# CH32V002J4M6.net
KiCad netlist of a schematic drawn in Altium Designer
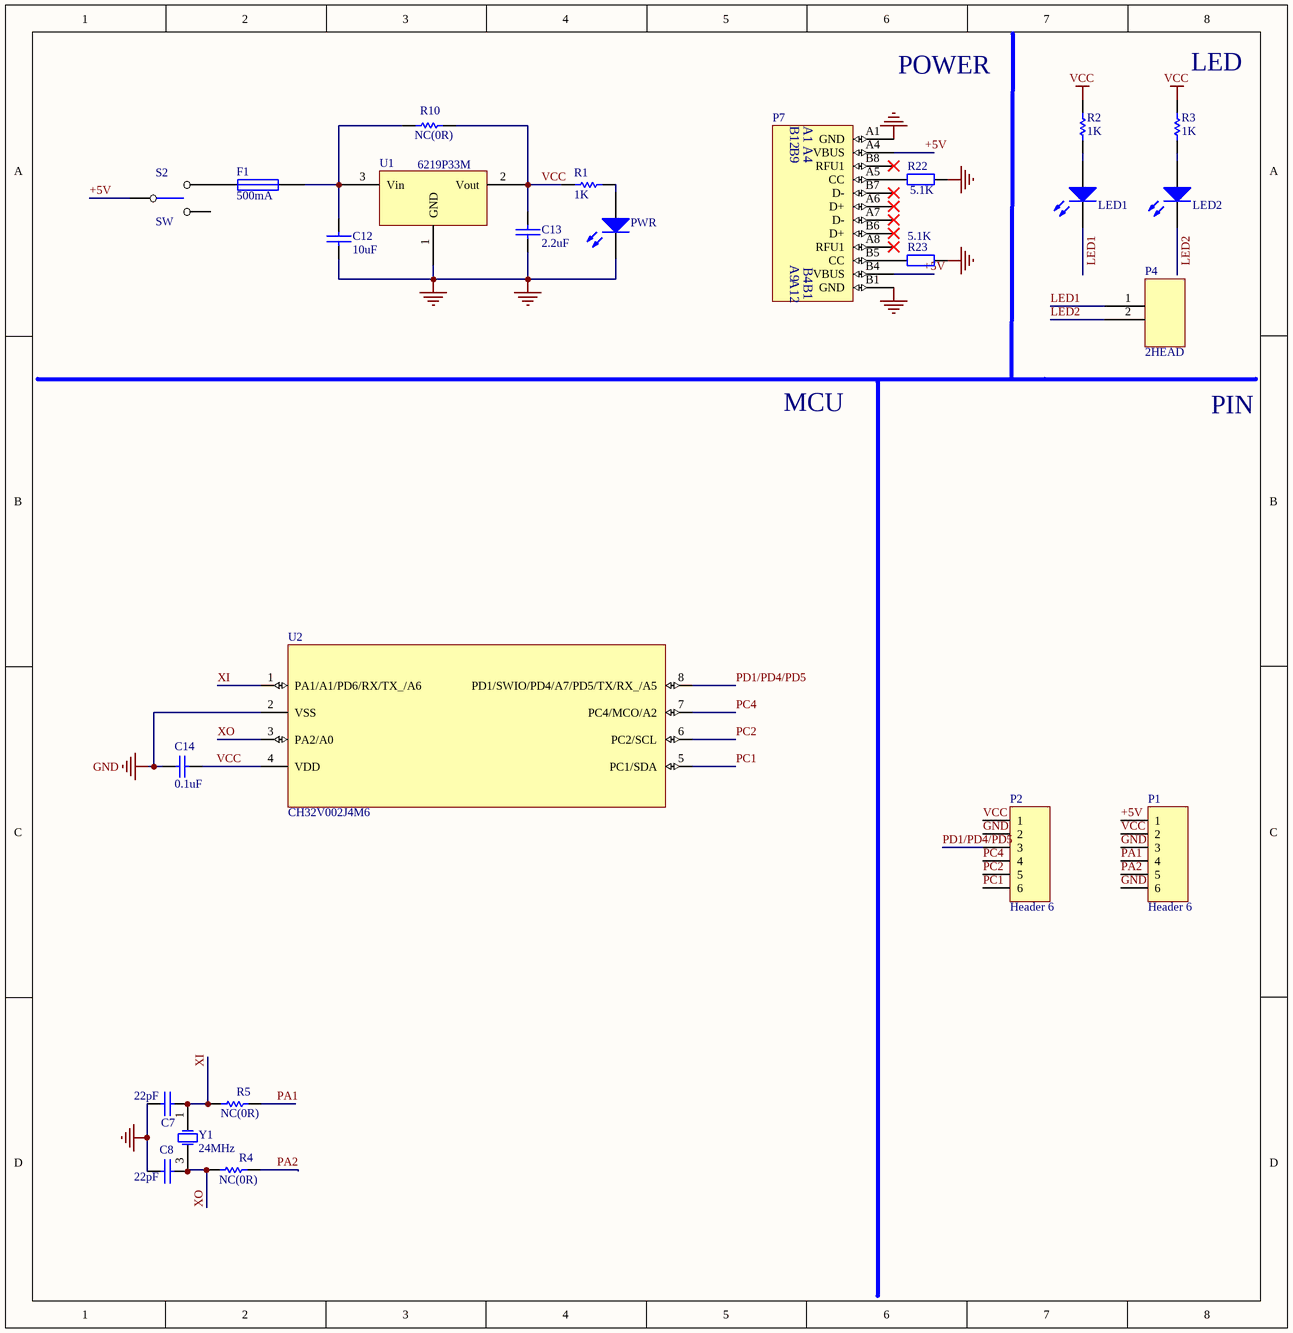
[diagram p0: CH32V002J4M6.SchDoc]

(export (version "E")
  (design (tool "Eeschema 10.0.6"))
  (components
    (comp (ref "C7")
      (value "22pF")
      (footprint "0402_C")
      (description "Capacitor")
      (libsource (lib "*") (part "CAP"))
    )
    (comp (ref "C8")
      (value "22pF")
      (footprint "0402_C")
      (description "Capacitor")
      (libsource (lib "*") (part "CAP"))
    )
    (comp (ref "C12")
      (value "10uF")
      (footprint "0603_C")
      (description "Capacitor")
      (libsource (lib "wch_sch_others") (part "CAP"))
    )
    (comp (ref "C13")
      (value "2.2uF")
      (footprint "0402_C")
      (description "Capacitor")
      (libsource (lib "wch_sch_others") (part "CAP"))
    )
    (comp (ref "C14")
      (value "0.1uF")
      (footprint "0603_C")
      (description "Capacitor")
      (fields (field (name "PUBLISHER") "Altium Limited"))
      (libsource (lib "*") (part "Cap"))
    )
    (comp (ref "F1")
      (value "500mA")
      (footprint "0603")
      (description "Fuse")
      (libsource (lib "*") (part "FUSE1"))
    )
    (comp (ref "LED1")
      (value "LED1   blue")
      (footprint "0603+")
      (description "Typical INFRARED GaAs LED")
      (fields (field (name "PUBLISHER") "Altium Limited"))
      (libsource (lib "") (part "LED0_1"))
    )
    (comp (ref "LED2")
      (value "LED2  blue")
      (footprint "0603+")
      (description "Typical INFRARED GaAs LED")
      (fields (field (name "PUBLISHER") "Altium Limited"))
      (libsource (lib "") (part "LED0_1"))
    )
    (comp (ref "P1")
      (value "Header 6")
      (footprint "HDR1X6")
      (description "Header, 6-Pin")
      (fields (field (name "PUBLISHER") "Altium Limited"))
      (libsource (lib "Miscellaneous Connectors") (part "Header 6"))
    )
    (comp (ref "P2")
      (value "Header 6")
      (footprint "HDR1X6")
      (description "Header, 6-Pin")
      (fields (field (name "PUBLISHER") "Altium Limited"))
      (libsource (lib "Miscellaneous Connectors") (part "Header 6"))
    )
    (comp (ref "P4") (value "2HEAD") (footprint "SIP2-2.54mm") (libsource (lib "*") (part "2HEAD")))
    (comp (ref "P7")
      (value "TYPE-C")
      (footprint "TYPE-C-Receptacle-2.0")
      (libsource (lib "*") (part "TYPE-C1"))
    )
    (comp (ref "PWR")
      (value "POWER  red")
      (footprint "0603+")
      (description "Typical INFRARED GaAs LED")
      (fields (field (name "PUBLISHER") "Altium Limited"))
      (libsource (lib "*") (part "LED0"))
    )
    (comp (ref "R1")
      (value "1K")
      (footprint "0402")
      (description "Semiconductor Resistor")
      (fields (field (name "PUBLISHER") "Altium Limited"))
      (libsource (lib "*") (part "Res Semi"))
    )
    (comp (ref "R2")
      (value "1K")
      (footprint "0402")
      (description "Semiconductor Resistor")
      (fields (field (name "PUBLISHER") "Altium Limited"))
      (libsource (lib "*") (part "Res Semi"))
    )
    (comp (ref "R3")
      (value "1K")
      (footprint "0402")
      (description "Semiconductor Resistor")
      (fields (field (name "PUBLISHER") "Altium Limited"))
      (libsource (lib "*") (part "Res Semi"))
    )
    (comp (ref "R4")
      (value "NC(0R)")
      (footprint "0402")
      (description "Semiconductor Resistor")
      (fields (field (name "Comment") "0R") (field (name "PUBLISHER") "Altium Limited"))
      (libsource (lib "*") (part "Res Semi"))
    )
    (comp (ref "R5")
      (value "NC(0R)")
      (footprint "0402")
      (description "Semiconductor Resistor")
      (fields (field (name "Comment") "0R") (field (name "PUBLISHER") "Altium Limited"))
      (libsource (lib "*") (part "Res Semi"))
    )
    (comp (ref "R10")
      (value "NC(0R)")
      (footprint "0402")
      (description "Semiconductor Resistor")
      (fields (field (name "Comment") "0R") (field (name "PUBLISHER") "Altium Limited"))
      (libsource (lib "*") (part "Res Semi"))
    )
    (comp (ref "R22")
      (value "5.1K")
      (footprint "0402")
      (description "Resistor")
      (libsource (lib "Miscellaneous Devices") (part "Res2"))
    )
    (comp (ref "R23")
      (value "5.1K")
      (footprint "0402")
      (description "Resistor")
      (libsource (lib "Miscellaneous Devices") (part "Res2"))
    )
    (comp (ref "S2") (value "SW") (footprint "SW1") (libsource (lib "*") (part "SW")))
    (comp (ref "U1")
      (value "6219P33M")
      (footprint "SOT-23")
      (libsource (lib "wch_sch_others") (part "6219P33M"))
    )
    (comp (ref "U2")
      (value "CH32V002J4M6")
      (footprint "SOP8")
      (description "RISC-V MCU, 48MHz, ADC/UART/I2C")
      (libsource (lib "DHXXXSCH") (part "CH32V002J4M6"))
    )
    (comp (ref "Y1")
      (value "24MHz")
      (footprint "XT3225")
      (description "Crystal Oscillator")
      (fields (field (name "PUBLISHER") "Altium Limited"))
      (libsource (lib "*") (part "XTAL"))
    )
  )
  (nets
    (net (code "1") (name "/+5V") (class "Default")
      (node (ref "P1") (pin "1") (pinfunction "1_1") (pintype "passive"))
      (node (ref "P7") (pin "A4") (pinfunction "VBUS_A4") (pintype "bidirectional"))
      (node (ref "P7") (pin "B4") (pinfunction "VBUS_B4") (pintype "bidirectional"))
      (node (ref "S2") (pin "1") (pinfunction "1_1") (pintype "passive"))
    )
    (net (code "2") (name "/LED1") (class "Default")
      (node (ref "LED1") (pin "2") (pinfunction "K_2") (pintype "passive"))
      (node (ref "P4") (pin "1") (pintype "passive"))
    )
    (net (code "3") (name "/LED2") (class "Default")
      (node (ref "LED2") (pin "2") (pinfunction "K_2") (pintype "passive"))
      (node (ref "P4") (pin "2") (pintype "passive"))
    )
    (net (code "4") (name "/PA1") (class "Default")
      (node (ref "P1") (pin "4") (pinfunction "4_4") (pintype "passive"))
      (node (ref "R5") (pin "2") (pinfunction "2_2") (pintype "passive"))
    )
    (net (code "5") (name "/PA2") (class "Default")
      (node (ref "P1") (pin "5") (pinfunction "5_5") (pintype "passive"))
      (node (ref "R4") (pin "2") (pinfunction "2_2") (pintype "passive"))
    )
    (net (code "6") (name "/PC1") (class "Default")
      (node (ref "P2") (pin "6") (pinfunction "6_6") (pintype "passive"))
      (node (ref "U2") (pin "5") (pinfunction "PC1/SDA_5") (pintype "bidirectional"))
    )
    (net (code "7") (name "/PC2") (class "Default")
      (node (ref "P2") (pin "5") (pinfunction "5_5") (pintype "passive"))
      (node (ref "U2") (pin "6") (pinfunction "PC2/SCL_6") (pintype "bidirectional"))
    )
    (net (code "8") (name "/PC4") (class "Default")
      (node (ref "P2") (pin "4") (pinfunction "4_4") (pintype "passive"))
      (node (ref "U2") (pin "7") (pinfunction "PC4/MCO/A2_7") (pintype "bidirectional"))
    )
    (net (code "9") (name "/PD1{slash}PD4{slash}PD5") (class "Default")
      (node (ref "P2") (pin "3") (pinfunction "3_3") (pintype "passive"))
      (node (ref "U2") (pin "8") (pinfunction "PD1/SWIO/PD4/A7/PD5/TX/RX_/A5_8") (pintype "bidirectional"))
    )
    (net (code "10") (name "/XI") (class "Default")
      (node (ref "C7") (pin "2") (pinfunction "2_2") (pintype "passive"))
      (node (ref "R5") (pin "1") (pinfunction "1_1") (pintype "passive"))
      (node (ref "U2") (pin "1") (pinfunction "PA1/A1/PD6/RX/TX_/A6_1") (pintype "bidirectional"))
      (node (ref "Y1") (pin "1") (pinfunction "OSC1_1") (pintype "passive"))
    )
    (net (code "11") (name "/XO") (class "Default")
      (node (ref "C8") (pin "2") (pinfunction "2_2") (pintype "passive"))
      (node (ref "R4") (pin "1") (pinfunction "1_1") (pintype "passive"))
      (node (ref "U2") (pin "3") (pinfunction "PA2/A0_3") (pintype "bidirectional"))
      (node (ref "Y1") (pin "3") (pinfunction "OSC2_3") (pintype "passive"))
    )
    (net (code "12") (name "GND") (class "Default")
      (node (ref "C12") (pin "2") (pinfunction "2_2") (pintype "passive"))
      (node (ref "C13") (pin "1") (pinfunction "1_1") (pintype "passive"))
      (node (ref "C14") (pin "2") (pinfunction "2_2") (pintype "passive"))
      (node (ref "C7") (pin "1") (pinfunction "1_1") (pintype "passive"))
      (node (ref "C8") (pin "1") (pinfunction "1_1") (pintype "passive"))
      (node (ref "P1") (pin "3") (pinfunction "3_3") (pintype "passive"))
      (node (ref "P1") (pin "6") (pinfunction "6_6") (pintype "passive"))
      (node (ref "P2") (pin "2") (pinfunction "2_2") (pintype "passive"))
      (node (ref "P7") (pin "A1") (pinfunction "GND_A1") (pintype "bidirectional"))
      (node (ref "P7") (pin "B1") (pinfunction "GND_B1") (pintype "bidirectional"))
      (node (ref "PWR") (pin "2") (pinfunction "K_2") (pintype "passive"))
      (node (ref "R22") (pin "2") (pinfunction "2_2") (pintype "passive"))
      (node (ref "R23") (pin "2") (pinfunction "2_2") (pintype "passive"))
      (node (ref "U1") (pin "1") (pinfunction "GND_1") (pintype "passive"))
      (node (ref "U2") (pin "2") (pinfunction "VSS_2") (pintype "power_in"))
    )
    (net (code "13") (name "Net-(F1-Pad1)") (class "Default")
      (node (ref "F1") (pin "1") (pinfunction "1_1") (pintype "passive"))
      (node (ref "S2") (pin "3") (pinfunction "3_3") (pintype "passive"))
    )
    (net (code "14") (name "Net-(LED1-A)") (class "Default")
      (node (ref "LED1") (pin "1") (pinfunction "A_1") (pintype "passive"))
      (node (ref "R2") (pin "2") (pinfunction "2_2") (pintype "passive"))
    )
    (net (code "15") (name "Net-(LED2-A)") (class "Default")
      (node (ref "LED2") (pin "1") (pinfunction "A_1") (pintype "passive"))
      (node (ref "R3") (pin "2") (pinfunction "2_2") (pintype "passive"))
    )
    (net (code "16") (name "Net-(P7-CC-PadA5)") (class "Default")
      (node (ref "P7") (pin "A5") (pinfunction "CC_A5") (pintype "bidirectional"))
      (node (ref "R22") (pin "1") (pinfunction "1_1") (pintype "passive"))
    )
    (net (code "17") (name "Net-(P7-CC-PadB5)") (class "Default")
      (node (ref "P7") (pin "B5") (pinfunction "CC_B5") (pintype "bidirectional"))
      (node (ref "R23") (pin "1") (pinfunction "1_1") (pintype "passive"))
    )
    (net (code "18") (name "Net-(PWR-A)") (class "Default")
      (node (ref "PWR") (pin "1") (pinfunction "A_1") (pintype "passive"))
      (node (ref "R1") (pin "1") (pinfunction "1_1") (pintype "passive"))
    )
    (net (code "19") (name "Net-(U1-Vin)") (class "Default")
      (node (ref "C12") (pin "1") (pinfunction "1_1") (pintype "passive"))
      (node (ref "F1") (pin "2") (pinfunction "2_2") (pintype "passive"))
      (node (ref "R10") (pin "1") (pinfunction "1_1") (pintype "passive"))
      (node (ref "U1") (pin "3") (pinfunction "Vin_3") (pintype "passive"))
    )
    (net (code "20") (name "VCC") (class "Default")
      (node (ref "C13") (pin "2") (pinfunction "2_2") (pintype "passive"))
      (node (ref "C14") (pin "1") (pinfunction "1_1") (pintype "passive"))
      (node (ref "P1") (pin "2") (pinfunction "2_2") (pintype "passive"))
      (node (ref "P2") (pin "1") (pinfunction "1_1") (pintype "passive"))
      (node (ref "R1") (pin "2") (pinfunction "2_2") (pintype "passive"))
      (node (ref "R10") (pin "2") (pinfunction "2_2") (pintype "passive"))
      (node (ref "R2") (pin "1") (pinfunction "1_1") (pintype "passive"))
      (node (ref "R3") (pin "1") (pinfunction "1_1") (pintype "passive"))
      (node (ref "U1") (pin "2") (pinfunction "Vout_2") (pintype "passive"))
      (node (ref "U2") (pin "4") (pinfunction "VDD_4") (pintype "power_in"))
    )
    (net (code "21") (name "unconnected-(P7-D+-PadA6)") (class "Default")
      (node (ref "P7") (pin "A6") (pinfunction "D+_A6") (pintype "bidirectional+no_connect"))
    )
    (net (code "22") (name "unconnected-(P7-D+-PadB6)") (class "Default")
      (node (ref "P7") (pin "B6") (pinfunction "D+_B6") (pintype "bidirectional+no_connect"))
    )
    (net (code "23") (name "unconnected-(P7-D--PadA7)") (class "Default")
      (node (ref "P7") (pin "A7") (pinfunction "D-_A7") (pintype "bidirectional+no_connect"))
    )
    (net (code "24") (name "unconnected-(P7-D--PadB7)") (class "Default")
      (node (ref "P7") (pin "B7") (pinfunction "D-_B7") (pintype "bidirectional+no_connect"))
    )
    (net (code "25") (name "unconnected-(P7-RFU1-PadA8)") (class "Default")
      (node (ref "P7") (pin "A8") (pinfunction "RFU1_A8") (pintype "bidirectional+no_connect"))
    )
    (net (code "26") (name "unconnected-(P7-RFU1-PadB8)") (class "Default")
      (node (ref "P7") (pin "B8") (pinfunction "RFU1_B8") (pintype "bidirectional+no_connect"))
    )
    (net (code "27") (name "unconnected-(S2-Pad2)") (class "Default")
      (node (ref "S2") (pin "2") (pinfunction "2_2") (pintype "passive"))
    )
  )
)
